# ICSP_breakout.net
KiCad netlist of a schematic drawn in Altium Designer
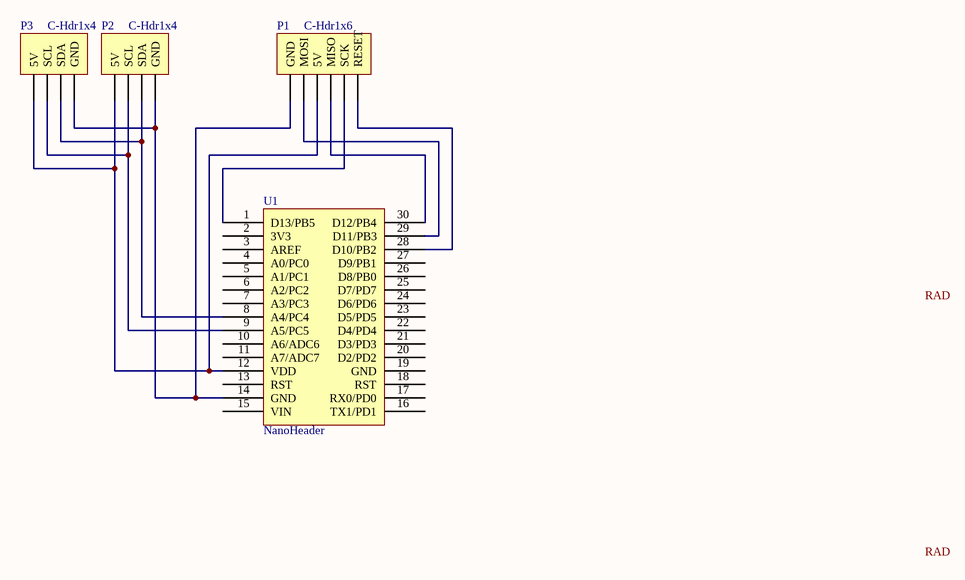
[diagram p0: ICSP_breakout.SchDoc]

(export (version "E")
  (design (tool "Eeschema 10.0.6"))
  (components
    (comp (ref "P1")
      (value "C-Hdr1x6")
      (footprint "HDR1X6_LGE1.0")
      (description "Header, 6-Pin")
      (fields (field (name "PUBLISHER") "Altium Limited"))
      (libsource (lib "PartsDatabaseV13p1") (part "C-Hdr1x6"))
    )
    (comp (ref "P2")
      (value "C-Hdr1x4")
      (footprint "HDR1X4_LGE1.0")
      (description "Header, 4-Pin")
      (fields (field (name "PUBLISHER") "Altium Limited"))
      (libsource (lib "PartsDatabaseV12") (part "C-Hdr1x4"))
    )
    (comp (ref "P3")
      (value "C-Hdr1x4")
      (footprint "HDR1X4_LGE1.0")
      (description "Header, 4-Pin")
      (fields (field (name "PUBLISHER") "Altium Limited"))
      (libsource (lib "PartsDatabaseV12") (part "C-Hdr1x4"))
    )
    (comp (ref "U1") (value "NanoHeader") (footprint "DIP30W") (libsource (lib "OpBots") (part "NanoHeader")))
  )
  (nets
    (net (code "2") (name "Net-(P1-5V)") (class "Default")
      (node (ref "P1") (pin "3") (pinfunction "5V_3") (pintype "passive"))
      (node (ref "P2") (pin "1") (pinfunction "5V_1") (pintype "passive"))
      (node (ref "P3") (pin "1") (pinfunction "5V_1") (pintype "passive"))
      (node (ref "U1") (pin "12") (pinfunction "VDD_12") (pintype "passive"))
    )
    (net (code "3") (name "Net-(P1-GND)") (class "Default")
      (node (ref "P1") (pin "1") (pinfunction "GND_1") (pintype "passive"))
      (node (ref "P2") (pin "4") (pinfunction "GND_4") (pintype "passive"))
      (node (ref "P3") (pin "4") (pinfunction "GND_4") (pintype "passive"))
      (node (ref "U1") (pin "14") (pinfunction "GND_14") (pintype "passive"))
    )
    (net (code "4") (name "Net-(P1-MISO)") (class "Default")
      (node (ref "P1") (pin "4") (pinfunction "MISO_4") (pintype "passive"))
      (node (ref "U1") (pin "30") (pinfunction "D12/PB4_30") (pintype "passive"))
    )
    (net (code "5") (name "Net-(P1-MOSI)") (class "Default")
      (node (ref "P1") (pin "2") (pinfunction "MOSI_2") (pintype "passive"))
      (node (ref "U1") (pin "29") (pinfunction "D11/PB3_29") (pintype "passive"))
    )
    (net (code "6") (name "Net-(P1-RESET)") (class "Default")
      (node (ref "P1") (pin "6") (pinfunction "RESET_6") (pintype "passive"))
      (node (ref "U1") (pin "28") (pinfunction "D10/PB2_28") (pintype "passive"))
    )
    (net (code "7") (name "Net-(P1-SCK)") (class "Default")
      (node (ref "P1") (pin "5") (pinfunction "SCK_5") (pintype "passive"))
      (node (ref "U1") (pin "1") (pinfunction "D13/PB5_1") (pintype "passive"))
    )
    (net (code "8") (name "Net-(P2-SCL)") (class "Default")
      (node (ref "P2") (pin "2") (pinfunction "SCL_2") (pintype "passive"))
      (node (ref "P3") (pin "2") (pinfunction "SCL_2") (pintype "passive"))
      (node (ref "U1") (pin "9") (pinfunction "A5/PC5_9") (pintype "passive"))
    )
    (net (code "9") (name "Net-(P2-SDA)") (class "Default")
      (node (ref "P2") (pin "3") (pinfunction "SDA_3") (pintype "passive"))
      (node (ref "P3") (pin "3") (pinfunction "SDA_3") (pintype "passive"))
      (node (ref "U1") (pin "8") (pinfunction "A4/PC4_8") (pintype "passive"))
    )
    (net (code "10") (name "unconnected-(U1-3V3-Pad2)") (class "Default")
      (node (ref "U1") (pin "2") (pinfunction "3V3_2") (pintype "passive"))
    )
    (net (code "11") (name "unconnected-(U1-A0{slash}PC0-Pad4)") (class "Default")
      (node (ref "U1") (pin "4") (pinfunction "A0/PC0_4") (pintype "passive"))
    )
    (net (code "12") (name "unconnected-(U1-A1{slash}PC1-Pad5)") (class "Default")
      (node (ref "U1") (pin "5") (pinfunction "A1/PC1_5") (pintype "passive"))
    )
    (net (code "13") (name "unconnected-(U1-A2{slash}PC2-Pad6)") (class "Default")
      (node (ref "U1") (pin "6") (pinfunction "A2/PC2_6") (pintype "passive"))
    )
    (net (code "14") (name "unconnected-(U1-A3{slash}PC3-Pad7)") (class "Default")
      (node (ref "U1") (pin "7") (pinfunction "A3/PC3_7") (pintype "passive"))
    )
    (net (code "15") (name "unconnected-(U1-A6{slash}ADC6-Pad10)") (class "Default")
      (node (ref "U1") (pin "10") (pinfunction "A6/ADC6_10") (pintype "passive"))
    )
    (net (code "16") (name "unconnected-(U1-A7{slash}ADC7-Pad11)") (class "Default")
      (node (ref "U1") (pin "11") (pinfunction "A7/ADC7_11") (pintype "passive"))
    )
    (net (code "17") (name "unconnected-(U1-AREF-Pad3)") (class "Default")
      (node (ref "U1") (pin "3") (pinfunction "AREF_3") (pintype "passive"))
    )
    (net (code "18") (name "unconnected-(U1-D2{slash}PD2-Pad20)") (class "Default")
      (node (ref "U1") (pin "20") (pinfunction "D2/PD2_20") (pintype "passive"))
    )
    (net (code "19") (name "unconnected-(U1-D3{slash}PD3-Pad21)") (class "Default")
      (node (ref "U1") (pin "21") (pinfunction "D3/PD3_21") (pintype "passive"))
    )
    (net (code "20") (name "unconnected-(U1-D4{slash}PD4-Pad22)") (class "Default")
      (node (ref "U1") (pin "22") (pinfunction "D4/PD4_22") (pintype "passive"))
    )
    (net (code "21") (name "unconnected-(U1-D5{slash}PD5-Pad23)") (class "Default")
      (node (ref "U1") (pin "23") (pinfunction "D5/PD5_23") (pintype "passive"))
    )
    (net (code "22") (name "unconnected-(U1-D6{slash}PD6-Pad24)") (class "Default")
      (node (ref "U1") (pin "24") (pinfunction "D6/PD6_24") (pintype "passive"))
    )
    (net (code "23") (name "unconnected-(U1-D7{slash}PD7-Pad25)") (class "Default")
      (node (ref "U1") (pin "25") (pinfunction "D7/PD7_25") (pintype "passive"))
    )
    (net (code "24") (name "unconnected-(U1-D8{slash}PB0-Pad26)") (class "Default")
      (node (ref "U1") (pin "26") (pinfunction "D8/PB0_26") (pintype "passive"))
    )
    (net (code "25") (name "unconnected-(U1-D9{slash}PB1-Pad27)") (class "Default")
      (node (ref "U1") (pin "27") (pinfunction "D9/PB1_27") (pintype "passive"))
    )
    (net (code "26") (name "unconnected-(U1-GND-Pad19)") (class "Default")
      (node (ref "U1") (pin "19") (pinfunction "GND_19") (pintype "passive"))
    )
    (net (code "27") (name "unconnected-(U1-RST-Pad13)") (class "Default")
      (node (ref "U1") (pin "13") (pinfunction "RST_13") (pintype "passive"))
    )
    (net (code "28") (name "unconnected-(U1-RST-Pad18)") (class "Default")
      (node (ref "U1") (pin "18") (pinfunction "RST_18") (pintype "passive"))
    )
    (net (code "29") (name "unconnected-(U1-RX0{slash}PD0-Pad17)") (class "Default")
      (node (ref "U1") (pin "17") (pinfunction "RX0/PD0_17") (pintype "passive"))
    )
    (net (code "30") (name "unconnected-(U1-TX1{slash}PD1-Pad16)") (class "Default")
      (node (ref "U1") (pin "16") (pinfunction "TX1/PD1_16") (pintype "passive"))
    )
    (net (code "31") (name "unconnected-(U1-VIN-Pad15)") (class "Default")
      (node (ref "U1") (pin "15") (pinfunction "VIN_15") (pintype "passive"))
    )
  )
)
